# 4G.net
KiCad netlist of a schematic drawn in Altium Designer
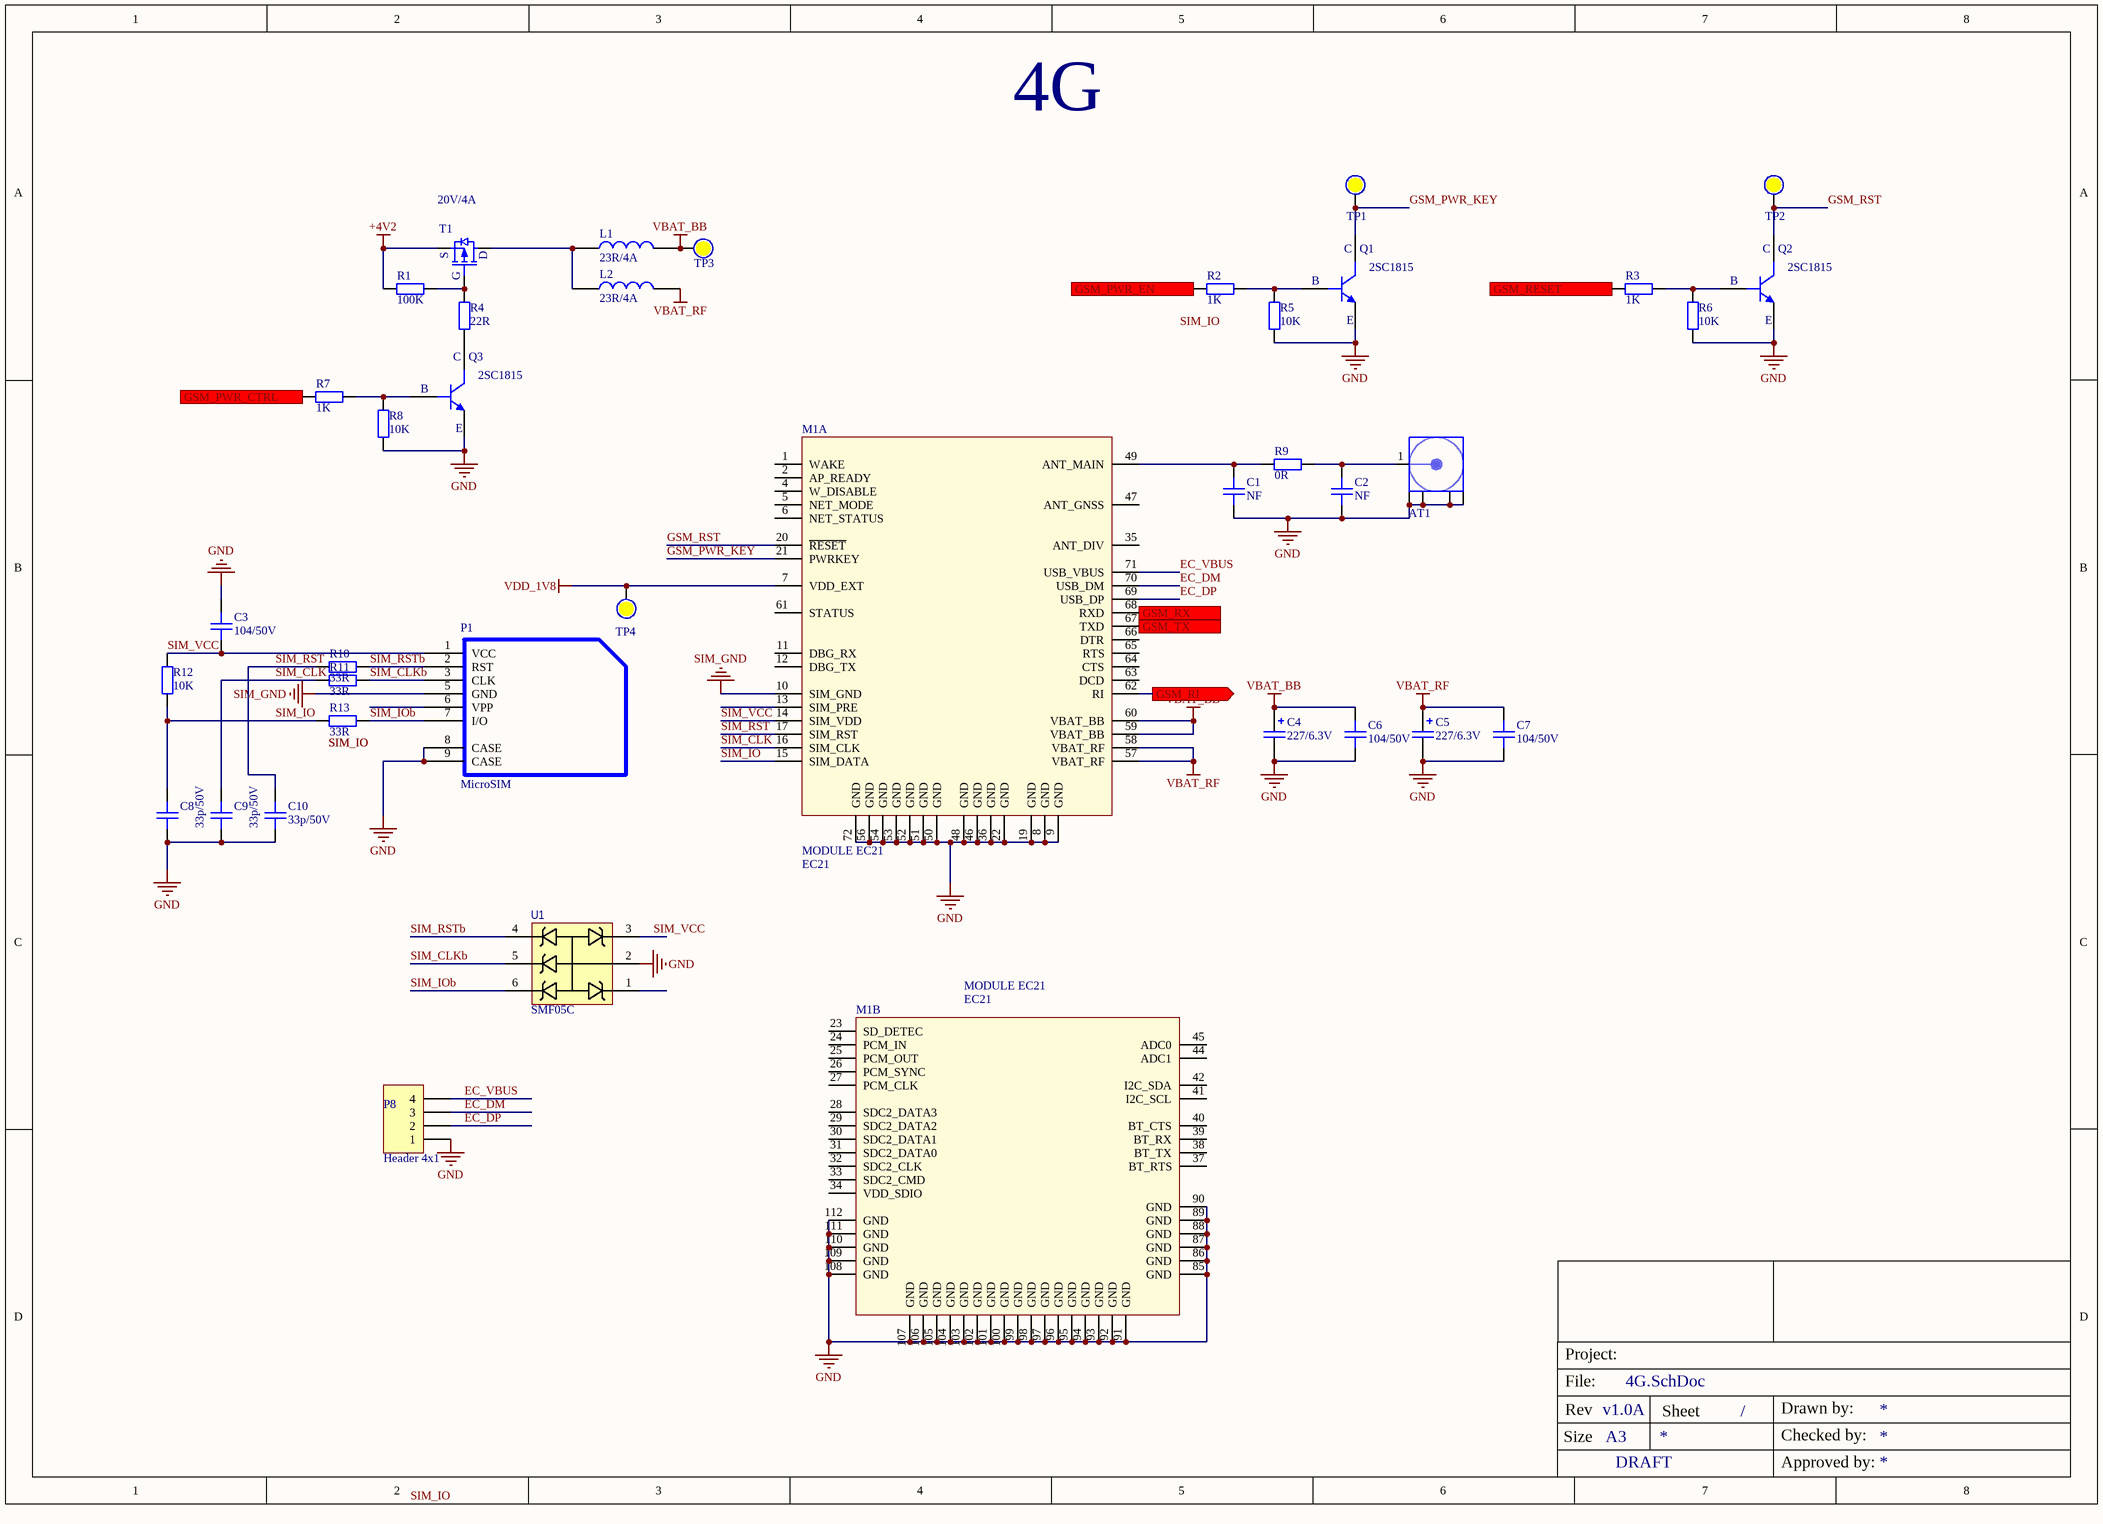
[diagram p0: 4G.SchDoc]

(export (version "E")
  (design (tool "Eeschema 10.0.6"))
  (components
    (comp (ref "AT1")
      (value "AT-GSM-GPS")
      (footprint "SNW_H11-L17-SMA")
      (description "CONNECTER ANTENNA GPS GSM")
      (fields (field (name "MPN") "SNW_H11-L17-SMA") (field (name "MFR") "Sunny Way"))
      (libsource (lib "lib") (part "SNW_H11-L17-SMA"))
    )
    (comp (ref "C1")
      (value "NF")
      (footprint "CAPC-0603 (1608)")
      (description "CAP SMD, Not Fill, 0603")
      (libsource (lib "lib") (part "CAPC NF 0603"))
    )
    (comp (ref "C2")
      (value "NF")
      (footprint "CAPC-0603 (1608)")
      (description "CAP SMD, Not Fill, 0603")
      (libsource (lib "lib") (part "CAPC NF 0603"))
    )
    (comp (ref "C3")
      (value "104/50V")
      (footprint "CAPC-0603 (1608)")
      (description "CAP CER 0.1uF 50V 10% X7R 0603")
      (fields (field (name "MPN") "C0603C104K5RACTU"))
      (libsource (lib "lib") (part "C0603C104K5RACTU"))
    )
    (comp (ref "C4")
      (value "227/6.3V")
      (footprint "CAP_TANTAL_1210(3528)")
      (description "CAP TANT POLY 220uF 20% 6.3V 3528 35mOhm ESR")
      (fields (field (name "MPN") "T520B227M006ATE035"))
      (libsource (lib "lib") (part "T520B227M006ATE035"))
    )
    (comp (ref "C5")
      (value "227/6.3V")
      (footprint "CAP_TANTAL_1210(3528)")
      (description "CAP TANT POLY 220uF 20% 6.3V 3528 35mOhm ESR")
      (fields (field (name "MPN") "T520B227M006ATE035"))
      (libsource (lib "lib") (part "T520B227M006ATE035"))
    )
    (comp (ref "C6")
      (value "104/50V")
      (footprint "CAPC-0603 (1608)")
      (description "CAP CER 0.1uF 50V 10% X7R 0603")
      (fields (field (name "MPN") "C0603C104K5RACTU"))
      (libsource (lib "lib") (part "C0603C104K5RACTU"))
    )
    (comp (ref "C7")
      (value "104/50V")
      (footprint "CAPC-0603 (1608)")
      (description "CAP CER 0.1uF 50V 10% X7R 0603")
      (fields (field (name "MPN") "C0603C104K5RACTU"))
      (libsource (lib "lib") (part "C0603C104K5RACTU"))
    )
    (comp (ref "C8")
      (value "33p/50V")
      (footprint "CAPC-0603 (1608)")
      (description "CAP CER 33pF 50V 5%  0603")
      (fields (field (name "MPN") "CL10C330JB8NNNC"))
      (libsource (lib "lib") (part "0603N330J500CT"))
    )
    (comp (ref "C9")
      (value "33p/50V")
      (footprint "CAPC-0603 (1608)")
      (description "CAP CER 33pF 50V 5%  0603")
      (fields (field (name "MPN") "CL10C330JB8NNNC"))
      (libsource (lib "lib") (part "0603N330J500CT"))
    )
    (comp (ref "C10")
      (value "33p/50V")
      (footprint "CAPC-0603 (1608)")
      (description "CAP CER 33pF 50V 5%  0603")
      (fields (field (name "MPN") "CL10C330JB8NNNC"))
      (libsource (lib "lib") (part "0603N330J500CT"))
    )
    (comp (ref "L1")
      (value "23R/4A")
      (footprint "IND-0603 (1608)")
      (description "IND-FERRITE BEAD 23 OHM  4A 0603 1LN")
      (fields (field (name "MPN") "FBMJ1608HM230NT"))
      (libsource (lib "lib") (part "FBMJ1608HM230NT"))
    )
    (comp (ref "L2")
      (value "23R/4A")
      (footprint "IND-0603 (1608)")
      (description "IND-FERRITE BEAD 23 OHM  4A 0603 1LN")
      (fields (field (name "MPN") "FBMJ1608HM230NT"))
      (libsource (lib "lib") (part "FBMJ1608HM230NT"))
    )
    (comp (ref "M1")
      (value "MODULE EC21")
      (footprint "QUECTEL_EC20")
      (description "Quectel EC21 is a series of LTE category")
      (fields (field (name "PART NUMBER") "EC21"))
      (libsource (lib "lib") (part "QUECTEL EC21"))
    )
    (comp (ref "P1")
      (value "MicroSIM")
      (footprint "MUP-C792")
      (description "MicroSIM Card Push - Push Holder")
      (fields (field (name "MFR") "MUP") (field (name "MPN") "C792"))
      (libsource (lib "lib") (part "MUP-C792"))
    )
    (comp (ref "P8")
      (value "Header 4x1")
      (footprint "HDR1X4")
      (description "Header, 4 Pin Pitch 2.54mm")
      (fields (field (name "MPN") "S1012EC-40-ND"))
      (libsource (lib "04.Header-Connecter") (part "Header 4x1"))
    )
    (comp (ref "Q1")
      (value "2SC1815")
      (footprint "SOT23_3")
      (description "TRANS NPN 50V 0.15A SOT23-3")
      (libsource (lib "lib") (part "2SC1815"))
    )
    (comp (ref "Q2")
      (value "2SC1815")
      (footprint "SOT23_3")
      (description "TRANS NPN 50V 0.15A SOT23-3")
      (libsource (lib "lib") (part "2SC1815"))
    )
    (comp (ref "Q3")
      (value "2SC1815")
      (footprint "SOT23_3")
      (description "TRANS NPN 50V 0.15A SOT23-3")
      (libsource (lib "lib") (part "2SC1815"))
    )
    (comp (ref "R1")
      (value "100K")
      (footprint "RESC-0603 (1608)")
      (description "RES SMD 100K OHM 1% 1/10W 0603")
      (fields (field (name "MPN") "RC0603FR-07100KL"))
      (libsource (lib "lib") (part "RC0603FR-07100KL"))
    )
    (comp (ref "R2")
      (value "1K")
      (footprint "RESC-0603 (1608)")
      (description "RES SMD 1 KOHM 1% 1/10W 0603")
      (fields (field (name "MPN") "RC0603FR-071KL"))
      (libsource (lib "lib") (part "RC0603FR-071KL"))
    )
    (comp (ref "R3")
      (value "1K")
      (footprint "RESC-0603 (1608)")
      (description "RES SMD 1 KOHM 1% 1/10W 0603")
      (fields (field (name "MPN") "RC0603FR-071KL"))
      (libsource (lib "lib") (part "RC0603FR-071KL"))
    )
    (comp (ref "R4")
      (value "22R")
      (footprint "RESC-0603 (1608)")
      (description "RES SMD 22 OHM 1% 1/10W 0603")
      (fields (field (name "MPN") "RC0603FR-0722RL"))
      (libsource (lib "lib") (part "RC0603FR-0722RL"))
    )
    (comp (ref "R5")
      (value "10K")
      (footprint "RESC-0603 (1608)")
      (description "RES SMD 10K OHM 1% 1/10W 0603")
      (fields (field (name "MPN") "RC0603FR-0710KL"))
      (libsource (lib "lib") (part "RC0603FR-0710KL"))
    )
    (comp (ref "R6")
      (value "10K")
      (footprint "RESC-0603 (1608)")
      (description "RES SMD 10K OHM 1% 1/10W 0603")
      (fields (field (name "MPN") "RC0603FR-0710KL"))
      (libsource (lib "lib") (part "RC0603FR-0710KL"))
    )
    (comp (ref "R7")
      (value "1K")
      (footprint "RESC-0603 (1608)")
      (description "RES SMD 1 KOHM 1% 1/10W 0603")
      (fields (field (name "MPN") "RC0603FR-071KL"))
      (libsource (lib "lib") (part "RC0603FR-071KL"))
    )
    (comp (ref "R8")
      (value "10K")
      (footprint "RESC-0603 (1608)")
      (description "RES SMD 10K OHM 1% 1/10W 0603")
      (fields (field (name "MPN") "RC0603FR-0710KL"))
      (libsource (lib "lib") (part "RC0603FR-0710KL"))
    )
    (comp (ref "R9")
      (value "0R")
      (footprint "RESC-0603 (1608)")
      (description "RES SMD 0.0OHM JUMPER 1/10W 0603")
      (fields (field (name "MPN") "RC0603FR-070RL"))
      (libsource (lib "lib") (part "RC0603FR-070RL"))
    )
    (comp (ref "R10")
      (value "33R")
      (footprint "RESC-0603 (1608)")
      (description "RES SMD 33 OHM 1% 1/10W 0603")
      (fields (field (name "MPN") "RC0603FR-0733RL") (field (name "MFR") "Yageo"))
      (libsource (lib "lib") (part "RC0603FR-0733RL"))
    )
    (comp (ref "R11")
      (value "33R")
      (footprint "RESC-0603 (1608)")
      (description "RES SMD 33 OHM 1% 1/10W 0603")
      (fields (field (name "MPN") "RC0603FR-0733RL") (field (name "MFR") "Yageo"))
      (libsource (lib "lib") (part "RC0603FR-0733RL"))
    )
    (comp (ref "R12")
      (value "10K")
      (footprint "RESC-0603 (1608)")
      (description "RES SMD 10K OHM 1% 1/10W 0603")
      (fields (field (name "MPN") "RC0603FR-0710KL"))
      (libsource (lib "lib") (part "RC0603FR-0710KL"))
    )
    (comp (ref "R13")
      (value "33R")
      (footprint "RESC-0603 (1608)")
      (description "RES SMD 33 OHM 1% 1/10W 0603")
      (fields (field (name "MPN") "RC0603FR-0733RL") (field (name "MFR") "Yageo"))
      (libsource (lib "lib") (part "RC0603FR-0733RL"))
    )
    (comp (ref "T1")
      (value "20V/4A")
      (footprint "SOT23_3")
      (description "MOSFET P-CH 20V 4A SOT23")
      (fields (field (name "MPN") "AO3415") (field (name "MFR") "Alpha & Omega Semiconductor Inc."))
      (libsource (lib "lib") (part "AO3415"))
    )
    (comp (ref "TP1")
      (value "~")
      (footprint "Test Point 1.5 MM")
      (description "Test Point")
      (libsource (lib "lib") (part "Test Point"))
    )
    (comp (ref "TP2")
      (value "~")
      (footprint "Test Point 1.5 MM")
      (description "Test Point")
      (libsource (lib "lib") (part "Test Point"))
    )
    (comp (ref "TP3")
      (value "~")
      (footprint "Test Point 1.5 MM")
      (description "Test Point")
      (libsource (lib "") (part "Test Point_1"))
    )
    (comp (ref "TP4")
      (value "~")
      (footprint "Test Point 1.5 MM")
      (description "Test Point")
      (libsource (lib "08.Miscellaneous") (part "Test Point"))
    )
    (comp (ref "U1")
      (value "SMF05C")
      (footprint "SOT65P210X140-6N")
      (description "TVS Diode Array For ESD and Latch-Up Protection")
      (fields (field (name "MFR") "ON SEMICONDUCTOR") (field (name "MPN") "SMF05CT2G"))
      (libsource (lib "lib") (part "SMF05C"))
    )
  )
  (nets
    (net (code "1") (name "+4V2") (class "Default")
      (node (ref "R1") (pin "1") (pinfunction "1_1") (pintype "passive"))
      (node (ref "T1") (pin "2") (pinfunction "S_2") (pintype "passive"))
    )
    (net (code "2") (name "/EC_DM") (class "Default")
      (node (ref "M1") (pin "70") (pinfunction "USB_DM_70") (pintype "passive"))
      (node (ref "P8") (pin "3") (pinfunction "3_3") (pintype "passive"))
    )
    (net (code "3") (name "/EC_DP") (class "Default")
      (node (ref "M1") (pin "69") (pinfunction "USB_DP_69") (pintype "passive"))
      (node (ref "P8") (pin "2") (pinfunction "2_2") (pintype "passive"))
    )
    (net (code "4") (name "/EC_VBUS") (class "Default")
      (node (ref "M1") (pin "71") (pinfunction "USB_VBUS_71") (pintype "passive"))
      (node (ref "P8") (pin "4") (pinfunction "4_4") (pintype "passive"))
    )
    (net (code "5") (name "/GSM_PWR_CTRL") (class "Default")
      (node (ref "R7") (pin "1") (pinfunction "1_1") (pintype "passive"))
    )
    (net (code "6") (name "/GSM_PWR_EN") (class "Default")
      (node (ref "R2") (pin "1") (pinfunction "1_1") (pintype "passive"))
    )
    (net (code "7") (name "/GSM_PWR_KEY") (class "Default")
      (node (ref "M1") (pin "21") (pinfunction "PWRKEY_21") (pintype "passive"))
      (node (ref "Q1") (pin "3") (pinfunction "C_3") (pintype "passive"))
      (node (ref "TP1") (pin "0") (pinfunction "0_0") (pintype "passive"))
    )
    (net (code "8") (name "/GSM_RESET") (class "Default")
      (node (ref "R3") (pin "1") (pinfunction "1_1") (pintype "passive"))
    )
    (net (code "9") (name "/GSM_RI") (class "Default")
      (node (ref "M1") (pin "62") (pinfunction "RI_62") (pintype "passive"))
    )
    (net (code "10") (name "/GSM_RST") (class "Default")
      (node (ref "M1") (pin "20") (pinfunction "~{RESET}_20") (pintype "passive"))
      (node (ref "Q2") (pin "3") (pinfunction "C_3") (pintype "passive"))
      (node (ref "TP2") (pin "0") (pinfunction "0_0") (pintype "passive"))
    )
    (net (code "11") (name "/GSM_RX") (class "Default")
      (node (ref "M1") (pin "68") (pinfunction "RXD_68") (pintype "passive"))
    )
    (net (code "12") (name "/GSM_TX") (class "Default")
      (node (ref "M1") (pin "67") (pinfunction "TXD_67") (pintype "passive"))
    )
    (net (code "13") (name "/SIM_CLK") (class "Default")
      (node (ref "C9") (pin "2") (pinfunction "2_2") (pintype "passive"))
      (node (ref "M1") (pin "16") (pinfunction "SIM_CLK_16") (pintype "passive"))
      (node (ref "R11") (pin "2") (pinfunction "2_2") (pintype "passive"))
    )
    (net (code "14") (name "/SIM_CLKb") (class "Default")
      (node (ref "P1") (pin "3") (pinfunction "CLK_3") (pintype "passive"))
      (node (ref "R11") (pin "1") (pinfunction "1_1") (pintype "passive"))
      (node (ref "U1") (pin "5") (pinfunction "CT4_5") (pintype "passive"))
    )
    (net (code "15") (name "/SIM_IO") (class "Default")
      (node (ref "C8") (pin "2") (pinfunction "2_2") (pintype "passive"))
      (node (ref "M1") (pin "15") (pinfunction "SIM_DATA_15") (pintype "passive"))
      (node (ref "R12") (pin "1") (pinfunction "1_1") (pintype "passive"))
      (node (ref "R13") (pin "2") (pinfunction "2_2") (pintype "passive"))
    )
    (net (code "16") (name "/SIM_IOb") (class "Default")
      (node (ref "P1") (pin "7") (pinfunction "I/O_7") (pintype "passive"))
      (node (ref "R13") (pin "1") (pinfunction "1_1") (pintype "passive"))
      (node (ref "U1") (pin "6") (pinfunction "CT5_6") (pintype "passive"))
    )
    (net (code "17") (name "/SIM_RST") (class "Default")
      (node (ref "C10") (pin "2") (pinfunction "2_2") (pintype "passive"))
      (node (ref "M1") (pin "17") (pinfunction "SIM_RST_17") (pintype "passive"))
      (node (ref "R10") (pin "2") (pinfunction "2_2") (pintype "passive"))
    )
    (net (code "18") (name "/SIM_RSTb") (class "Default")
      (node (ref "P1") (pin "2") (pinfunction "RST_2") (pintype "passive"))
      (node (ref "R10") (pin "1") (pinfunction "1_1") (pintype "passive"))
      (node (ref "U1") (pin "4") (pinfunction "CT3_4") (pintype "passive"))
    )
    (net (code "19") (name "/SIM_VCC") (class "Default")
      (node (ref "C3") (pin "1") (pinfunction "1_1") (pintype "passive"))
      (node (ref "M1") (pin "14") (pinfunction "SIM_VDD_14") (pintype "passive"))
      (node (ref "P1") (pin "1") (pinfunction "VCC_1") (pintype "passive"))
      (node (ref "R12") (pin "2") (pinfunction "2_2") (pintype "passive"))
      (node (ref "U1") (pin "3") (pinfunction "CT2_3") (pintype "passive"))
    )
    (net (code "20") (name "GND") (class "Default")
      (node (ref "AT1") (pin "2") (pinfunction "2_2") (pintype "power_in"))
      (node (ref "C1") (pin "1") (pinfunction "1_1") (pintype "passive"))
      (node (ref "C10") (pin "1") (pinfunction "1_1") (pintype "passive"))
      (node (ref "C2") (pin "1") (pinfunction "1_1") (pintype "passive"))
      (node (ref "C3") (pin "2") (pinfunction "2_2") (pintype "passive"))
      (node (ref "C4") (pin "2") (pinfunction "2_2") (pintype "passive"))
      (node (ref "C5") (pin "2") (pinfunction "2_2") (pintype "passive"))
      (node (ref "C6") (pin "1") (pinfunction "1_1") (pintype "passive"))
      (node (ref "C7") (pin "1") (pinfunction "1_1") (pintype "passive"))
      (node (ref "C8") (pin "1") (pinfunction "1_1") (pintype "passive"))
      (node (ref "C9") (pin "1") (pinfunction "1_1") (pintype "passive"))
      (node (ref "M1") (pin "100") (pinfunction "GND_100") (pintype "passive"))
      (node (ref "M1") (pin "101") (pinfunction "GND_101") (pintype "passive"))
      (node (ref "M1") (pin "102") (pinfunction "GND_102") (pintype "passive"))
      (node (ref "M1") (pin "103") (pinfunction "GND_103") (pintype "passive"))
      (node (ref "M1") (pin "104") (pinfunction "GND_104") (pintype "passive"))
      (node (ref "M1") (pin "105") (pinfunction "GND_105") (pintype "passive"))
      (node (ref "M1") (pin "106") (pinfunction "GND_106") (pintype "passive"))
      (node (ref "M1") (pin "107") (pinfunction "GND_107") (pintype "passive"))
      (node (ref "M1") (pin "108") (pinfunction "GND_108") (pintype "passive"))
      (node (ref "M1") (pin "109") (pinfunction "GND_109") (pintype "passive"))
      (node (ref "M1") (pin "110") (pinfunction "GND_110") (pintype "passive"))
      (node (ref "M1") (pin "111") (pinfunction "GND_111") (pintype "passive"))
      (node (ref "M1") (pin "112") (pinfunction "GND_112") (pintype "passive"))
      (node (ref "M1") (pin "19") (pinfunction "GND_19") (pintype "passive"))
      (node (ref "M1") (pin "22") (pinfunction "GND_22") (pintype "passive"))
      (node (ref "M1") (pin "36") (pinfunction "GND_36") (pintype "passive"))
      (node (ref "M1") (pin "46") (pinfunction "GND_46") (pintype "passive"))
      (node (ref "M1") (pin "48") (pinfunction "GND_48") (pintype "passive"))
      (node (ref "M1") (pin "50") (pinfunction "GND_50") (pintype "passive"))
      (node (ref "M1") (pin "51") (pinfunction "GND_51") (pintype "passive"))
      (node (ref "M1") (pin "52") (pinfunction "GND_52") (pintype "passive"))
      (node (ref "M1") (pin "53") (pinfunction "GND_53") (pintype "passive"))
      (node (ref "M1") (pin "54") (pinfunction "GND_54") (pintype "passive"))
      (node (ref "M1") (pin "56") (pinfunction "GND_56") (pintype "passive"))
      (node (ref "M1") (pin "72") (pinfunction "GND_72") (pintype "passive"))
      (node (ref "M1") (pin "8") (pinfunction "GND_8") (pintype "passive"))
      (node (ref "M1") (pin "85") (pinfunction "GND_85") (pintype "passive"))
      (node (ref "M1") (pin "86") (pinfunction "GND_86") (pintype "passive"))
      (node (ref "M1") (pin "87") (pinfunction "GND_87") (pintype "passive"))
      (node (ref "M1") (pin "88") (pinfunction "GND_88") (pintype "passive"))
      (node (ref "M1") (pin "89") (pinfunction "GND_89") (pintype "passive"))
      (node (ref "M1") (pin "9") (pinfunction "GND_9") (pintype "passive"))
      (node (ref "M1") (pin "90") (pinfunction "GND_90") (pintype "passive"))
      (node (ref "M1") (pin "91") (pinfunction "GND_91") (pintype "passive"))
      (node (ref "M1") (pin "92") (pinfunction "GND_92") (pintype "passive"))
      (node (ref "M1") (pin "93") (pinfunction "GND_93") (pintype "passive"))
      (node (ref "M1") (pin "94") (pinfunction "GND_94") (pintype "passive"))
      (node (ref "M1") (pin "95") (pinfunction "GND_95") (pintype "passive"))
      (node (ref "M1") (pin "96") (pinfunction "GND_96") (pintype "passive"))
      (node (ref "M1") (pin "97") (pinfunction "GND_97") (pintype "passive"))
      (node (ref "M1") (pin "98") (pinfunction "GND_98") (pintype "passive"))
      (node (ref "M1") (pin "99") (pinfunction "GND_99") (pintype "passive"))
      (node (ref "P1") (pin "8") (pinfunction "CASE_8") (pintype "passive"))
      (node (ref "P1") (pin "9") (pinfunction "CASE_9") (pintype "passive"))
      (node (ref "P8") (pin "1") (pinfunction "1_1") (pintype "passive"))
      (node (ref "Q1") (pin "2") (pinfunction "E_2") (pintype "passive"))
      (node (ref "Q2") (pin "2") (pinfunction "E_2") (pintype "passive"))
      (node (ref "Q3") (pin "2") (pinfunction "E_2") (pintype "passive"))
      (node (ref "R5") (pin "1") (pinfunction "1_1") (pintype "passive"))
      (node (ref "R6") (pin "1") (pinfunction "1_1") (pintype "passive"))
      (node (ref "R8") (pin "1") (pinfunction "1_1") (pintype "passive"))
      (node (ref "U1") (pin "2") (pinfunction "AN_2") (pintype "passive"))
    )
    (net (code "21") (name "Net-(AT1-Signal)") (class "Default")
      (node (ref "AT1") (pin "1") (pinfunction "Signal_1") (pintype "passive"))
      (node (ref "C2") (pin "2") (pinfunction "2_2") (pintype "passive"))
      (node (ref "R9") (pin "2") (pinfunction "2_2") (pintype "passive"))
    )
    (net (code "22") (name "Net-(M1A-ANT_MAIN)") (class "Default")
      (node (ref "C1") (pin "2") (pinfunction "2_2") (pintype "passive"))
      (node (ref "M1") (pin "49") (pinfunction "ANT_MAIN_49") (pintype "passive"))
      (node (ref "R9") (pin "1") (pinfunction "1_1") (pintype "passive"))
    )
    (net (code "23") (name "Net-(Q1-B)") (class "Default")
      (node (ref "Q1") (pin "1") (pinfunction "B_1") (pintype "passive"))
      (node (ref "R2") (pin "2") (pinfunction "2_2") (pintype "passive"))
      (node (ref "R5") (pin "2") (pinfunction "2_2") (pintype "passive"))
    )
    (net (code "24") (name "Net-(Q2-B)") (class "Default")
      (node (ref "Q2") (pin "1") (pinfunction "B_1") (pintype "passive"))
      (node (ref "R3") (pin "2") (pinfunction "2_2") (pintype "passive"))
      (node (ref "R6") (pin "2") (pinfunction "2_2") (pintype "passive"))
    )
    (net (code "25") (name "Net-(Q3-B)") (class "Default")
      (node (ref "Q3") (pin "1") (pinfunction "B_1") (pintype "passive"))
      (node (ref "R7") (pin "2") (pinfunction "2_2") (pintype "passive"))
      (node (ref "R8") (pin "2") (pinfunction "2_2") (pintype "passive"))
    )
    (net (code "26") (name "Net-(Q3-C)") (class "Default")
      (node (ref "Q3") (pin "3") (pinfunction "C_3") (pintype "passive"))
      (node (ref "R4") (pin "1") (pinfunction "1_1") (pintype "passive"))
    )
    (net (code "27") (name "Net-(T1-D)") (class "Default")
      (node (ref "L1") (pin "1") (pinfunction "1_1") (pintype "passive"))
      (node (ref "L2") (pin "1") (pinfunction "1_1") (pintype "passive"))
      (node (ref "T1") (pin "3") (pinfunction "D_3") (pintype "passive"))
    )
    (net (code "28") (name "Net-(T1-G)") (class "Default")
      (node (ref "R1") (pin "2") (pinfunction "2_2") (pintype "passive"))
      (node (ref "R4") (pin "2") (pinfunction "2_2") (pintype "passive"))
      (node (ref "T1") (pin "1") (pinfunction "G_1") (pintype "passive"))
    )
    (net (code "29") (name "SIM_GND") (class "Default")
      (node (ref "M1") (pin "10") (pinfunction "SIM_GND_10") (pintype "passive"))
      (node (ref "P1") (pin "5") (pinfunction "GND_5") (pintype "passive"))
    )
    (net (code "30") (name "VBAT_BB") (class "Default")
      (node (ref "C4") (pin "1") (pinfunction "1_1") (pintype "passive"))
      (node (ref "C6") (pin "2") (pinfunction "2_2") (pintype "passive"))
      (node (ref "L1") (pin "2") (pinfunction "2_2") (pintype "passive"))
      (node (ref "M1") (pin "59") (pinfunction "VBAT_BB_59") (pintype "passive"))
      (node (ref "M1") (pin "60") (pinfunction "VBAT_BB_60") (pintype "passive"))
      (node (ref "TP3") (pin "0") (pinfunction "0_0") (pintype "passive"))
    )
    (net (code "31") (name "VBAT_RF") (class "Default")
      (node (ref "C5") (pin "1") (pinfunction "1_1") (pintype "passive"))
      (node (ref "C7") (pin "2") (pinfunction "2_2") (pintype "passive"))
      (node (ref "L2") (pin "2") (pinfunction "2_2") (pintype "passive"))
      (node (ref "M1") (pin "57") (pinfunction "VBAT_RF_57") (pintype "passive"))
      (node (ref "M1") (pin "58") (pinfunction "VBAT_RF_58") (pintype "passive"))
    )
    (net (code "32") (name "VDD_1V8") (class "Default")
      (node (ref "M1") (pin "7") (pinfunction "VDD_EXT_7") (pintype "passive"))
      (node (ref "TP4") (pin "0") (pinfunction "0_0") (pintype "passive"))
    )
    (net (code "33") (name "unconnected-(AT1-Pad2)") (class "Default")
      (node (ref "AT1") (pin "2") (pinfunction "2_2") (pintype "passive"))
    )
    (net (code "34") (name "unconnected-(M1A-ANT_DIV-Pad35)") (class "Default")
      (node (ref "M1") (pin "35") (pinfunction "ANT_DIV_35") (pintype "passive"))
    )
    (net (code "35") (name "unconnected-(M1A-ANT_GNSS-Pad47)") (class "Default")
      (node (ref "M1") (pin "47") (pinfunction "ANT_GNSS_47") (pintype "passive"))
    )
    (net (code "36") (name "unconnected-(M1A-AP_READY-Pad2)") (class "Default")
      (node (ref "M1") (pin "2") (pinfunction "AP_READY_2") (pintype "passive"))
    )
    (net (code "37") (name "unconnected-(M1A-CTS-Pad64)") (class "Default")
      (node (ref "M1") (pin "64") (pinfunction "CTS_64") (pintype "passive"))
    )
    (net (code "38") (name "unconnected-(M1A-DBG_RX-Pad11)") (class "Default")
      (node (ref "M1") (pin "11") (pinfunction "DBG_RX_11") (pintype "passive"))
    )
    (net (code "39") (name "unconnected-(M1A-DBG_TX-Pad12)") (class "Default")
      (node (ref "M1") (pin "12") (pinfunction "DBG_TX_12") (pintype "passive"))
    )
    (net (code "40") (name "unconnected-(M1A-DCD-Pad63)") (class "Default")
      (node (ref "M1") (pin "63") (pinfunction "DCD_63") (pintype "passive"))
    )
    (net (code "41") (name "unconnected-(M1A-DTR-Pad66)") (class "Default")
      (node (ref "M1") (pin "66") (pinfunction "DTR_66") (pintype "passive"))
    )
    (net (code "42") (name "unconnected-(M1A-NET_MODE-Pad5)") (class "Default")
      (node (ref "M1") (pin "5") (pinfunction "NET_MODE_5") (pintype "passive"))
    )
    (net (code "43") (name "unconnected-(M1A-NET_STATUS-Pad6)") (class "Default")
      (node (ref "M1") (pin "6") (pinfunction "NET_STATUS_6") (pintype "passive"))
    )
    (net (code "44") (name "unconnected-(M1A-RTS-Pad65)") (class "Default")
      (node (ref "M1") (pin "65") (pinfunction "RTS_65") (pintype "passive"))
    )
    (net (code "45") (name "unconnected-(M1A-SIM_PRE-Pad13)") (class "Default")
      (node (ref "M1") (pin "13") (pinfunction "SIM_PRE_13") (pintype "passive"))
    )
    (net (code "46") (name "unconnected-(M1A-STATUS-Pad61)") (class "Default")
      (node (ref "M1") (pin "61") (pinfunction "STATUS_61") (pintype "passive"))
    )
    (net (code "47") (name "unconnected-(M1A-WAKE-Pad1)") (class "Default")
      (node (ref "M1") (pin "1") (pinfunction "WAKE_1") (pintype "passive"))
    )
    (net (code "48") (name "unconnected-(M1A-W_DISABLE-Pad4)") (class "Default")
      (node (ref "M1") (pin "4") (pinfunction "W_DISABLE_4") (pintype "passive"))
    )
    (net (code "49") (name "unconnected-(M1B-ADC0-Pad45)") (class "Default")
      (node (ref "M1") (pin "45") (pinfunction "ADC0_45") (pintype "passive"))
    )
    (net (code "50") (name "unconnected-(M1B-ADC1-Pad44)") (class "Default")
      (node (ref "M1") (pin "44") (pinfunction "ADC1_44") (pintype "passive"))
    )
    (net (code "51") (name "unconnected-(M1B-BT_CTS-Pad40)") (class "Default")
      (node (ref "M1") (pin "40") (pinfunction "BT_CTS_40") (pintype "passive"))
    )
    (net (code "52") (name "unconnected-(M1B-BT_RTS-Pad37)") (class "Default")
      (node (ref "M1") (pin "37") (pinfunction "BT_RTS_37") (pintype "passive"))
    )
    (net (code "53") (name "unconnected-(M1B-BT_RX-Pad39)") (class "Default")
      (node (ref "M1") (pin "39") (pinfunction "BT_RX_39") (pintype "passive"))
    )
    (net (code "54") (name "unconnected-(M1B-BT_TX-Pad38)") (class "Default")
      (node (ref "M1") (pin "38") (pinfunction "BT_TX_38") (pintype "passive"))
    )
    (net (code "55") (name "unconnected-(M1B-I2C_SCL-Pad41)") (class "Default")
      (node (ref "M1") (pin "41") (pinfunction "I2C_SCL_41") (pintype "passive"))
    )
    (net (code "56") (name "unconnected-(M1B-I2C_SDA-Pad42)") (class "Default")
      (node (ref "M1") (pin "42") (pinfunction "I2C_SDA_42") (pintype "passive"))
    )
    (net (code "57") (name "unconnected-(M1B-PCM_CLK-Pad27)") (class "Default")
      (node (ref "M1") (pin "27") (pinfunction "PCM_CLK_27") (pintype "passive"))
    )
    (net (code "58") (name "unconnected-(M1B-PCM_IN-Pad24)") (class "Default")
      (node (ref "M1") (pin "24") (pinfunction "PCM_IN_24") (pintype "passive"))
    )
    (net (code "59") (name "unconnected-(M1B-PCM_OUT-Pad25)") (class "Default")
      (node (ref "M1") (pin "25") (pinfunction "PCM_OUT_25") (pintype "passive"))
    )
    (net (code "60") (name "unconnected-(M1B-PCM_SYNC-Pad26)") (class "Default")
      (node (ref "M1") (pin "26") (pinfunction "PCM_SYNC_26") (pintype "passive"))
    )
    (net (code "61") (name "unconnected-(M1B-SDC2_CLK-Pad32)") (class "Default")
      (node (ref "M1") (pin "32") (pinfunction "SDC2_CLK_32") (pintype "passive"))
    )
    (net (code "62") (name "unconnected-(M1B-SDC2_CMD-Pad33)") (class "Default")
      (node (ref "M1") (pin "33") (pinfunction "SDC2_CMD_33") (pintype "passive"))
    )
    (net (code "63") (name "unconnected-(M1B-SDC2_DATA0-Pad31)") (class "Default")
      (node (ref "M1") (pin "31") (pinfunction "SDC2_DATA0_31") (pintype "passive"))
    )
    (net (code "64") (name "unconnected-(M1B-SDC2_DATA1-Pad30)") (class "Default")
      (node (ref "M1") (pin "30") (pinfunction "SDC2_DATA1_30") (pintype "passive"))
    )
    (net (code "65") (name "unconnected-(M1B-SDC2_DATA2-Pad29)") (class "Default")
      (node (ref "M1") (pin "29") (pinfunction "SDC2_DATA2_29") (pintype "passive"))
    )
    (net (code "66") (name "unconnected-(M1B-SDC2_DATA3-Pad28)") (class "Default")
      (node (ref "M1") (pin "28") (pinfunction "SDC2_DATA3_28") (pintype "passive"))
    )
    (net (code "67") (name "unconnected-(M1B-SD_DETEC-Pad23)") (class "Default")
      (node (ref "M1") (pin "23") (pinfunction "SD_DETEC_23") (pintype "passive"))
    )
    (net (code "68") (name "unconnected-(M1B-VDD_SDIO-Pad34)") (class "Default")
      (node (ref "M1") (pin "34") (pinfunction "VDD_SDIO_34") (pintype "passive"))
    )
    (net (code "69") (name "unconnected-(P1-VPP-Pad6)") (class "Default")
      (node (ref "P1") (pin "6") (pinfunction "VPP_6") (pintype "passive"))
    )
    (net (code "70") (name "unconnected-(U1-CT1-Pad1)") (class "Default")
      (node (ref "U1") (pin "1") (pinfunction "CT1_1") (pintype "passive"))
    )
  )
)
